# 2_power_a.net
KiCad netlist of a schematic drawn in EAGLE
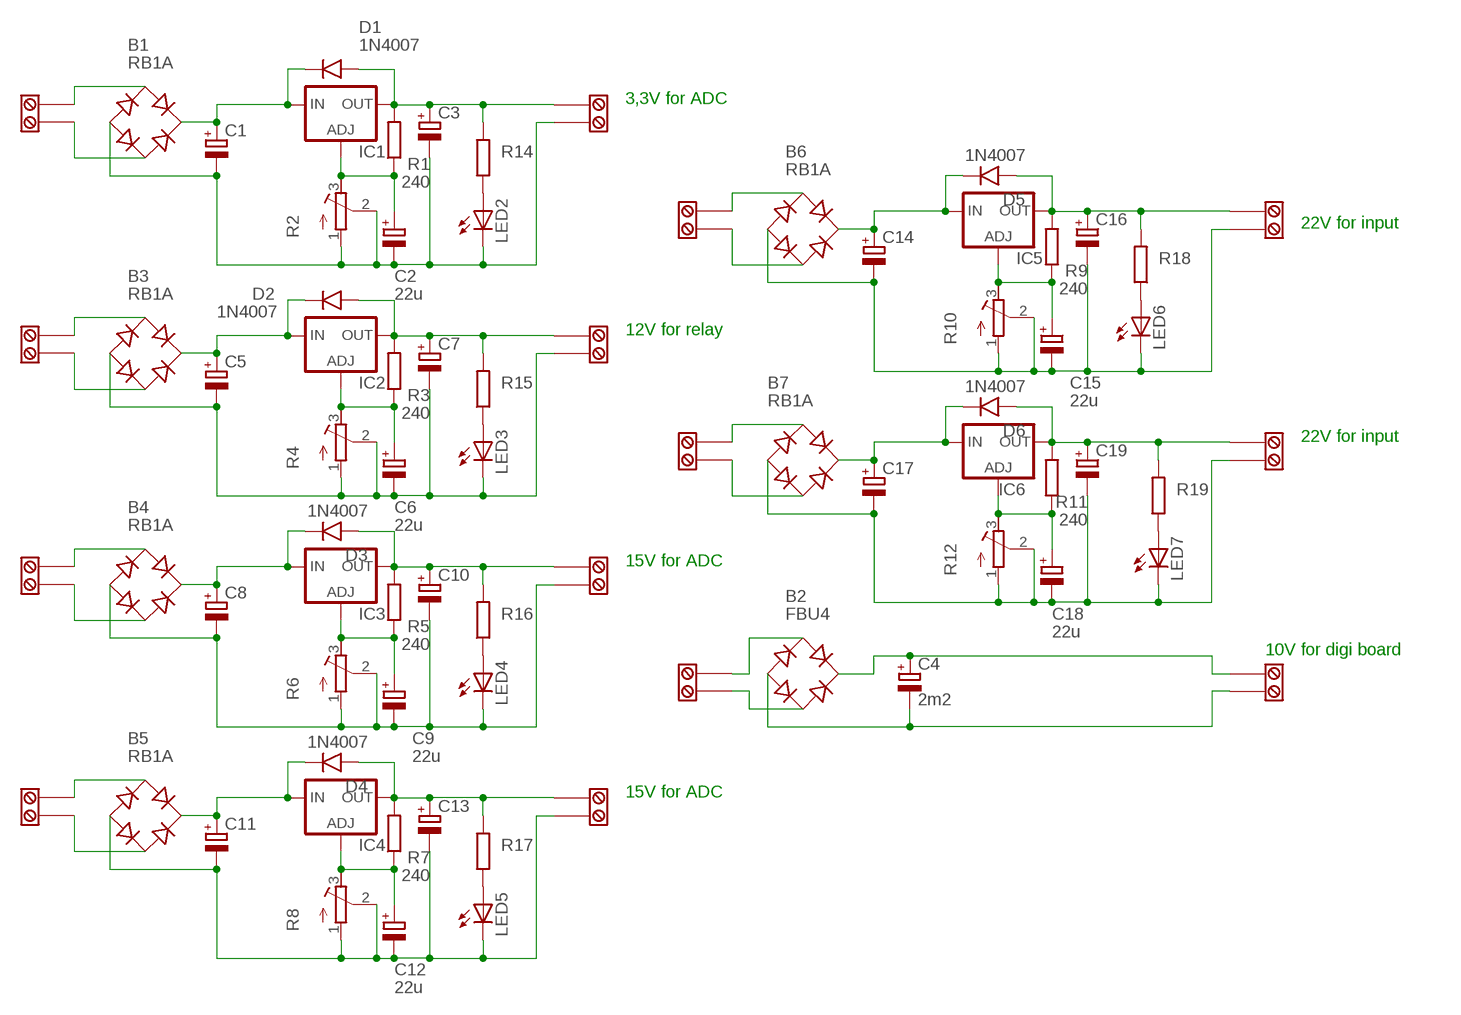
[diagram p0: schematic, sheet 1]

(export (version "E")
  (design (tool "Eeschema 10.0.6"))
  (components
    (comp (ref "B1")
      (value "RB1A")
      (footprint "eagle-import:RB1A")
      (libsource (lib "eagle-import") (part "RECTIFIER-RB1A"))
    )
    (comp (ref "B2")
      (value "FBU4")
      (footprint "eagle-import:FBU4")
      (libsource (lib "eagle-import") (part "RECTIFIER-FBU4"))
    )
    (comp (ref "B3")
      (value "RB1A")
      (footprint "eagle-import:RB1A")
      (libsource (lib "eagle-import") (part "RECTIFIER-RB1A"))
    )
    (comp (ref "B4")
      (value "RB1A")
      (footprint "eagle-import:RB1A")
      (libsource (lib "eagle-import") (part "RECTIFIER-RB1A"))
    )
    (comp (ref "B5")
      (value "RB1A")
      (footprint "eagle-import:RB1A")
      (libsource (lib "eagle-import") (part "RECTIFIER-RB1A"))
    )
    (comp (ref "B6")
      (value "RB1A")
      (footprint "eagle-import:RB1A")
      (libsource (lib "eagle-import") (part "RECTIFIER-RB1A"))
    )
    (comp (ref "B7")
      (value "RB1A")
      (footprint "eagle-import:RB1A")
      (libsource (lib "eagle-import") (part "RECTIFIER-RB1A"))
    )
    (comp (ref "C1")
      (value "CPOL-EUE5-10.5")
      (footprint "eagle-import:E5-10,5")
      (libsource (lib "eagle-import") (part "CPOL-EUE5-10.5"))
    )
    (comp (ref "C2")
      (value "22u")
      (footprint "eagle-import:E2,5-6")
      (libsource (lib "eagle-import") (part "CPOL-EUE2.5-6"))
    )
    (comp (ref "C3")
      (value "CPOL-EUE3.5-8")
      (footprint "eagle-import:E3,5-8")
      (libsource (lib "eagle-import") (part "CPOL-EUE3.5-8"))
    )
    (comp (ref "C4")
      (value "2m2")
      (footprint "eagle-import:E5-13")
      (libsource (lib "eagle-import") (part "CPOL-EUE5-13"))
    )
    (comp (ref "C5")
      (value "CPOL-EUE5-10.5")
      (footprint "eagle-import:E5-10,5")
      (libsource (lib "eagle-import") (part "CPOL-EUE5-10.5"))
    )
    (comp (ref "C6")
      (value "22u")
      (footprint "eagle-import:E2,5-6")
      (libsource (lib "eagle-import") (part "CPOL-EUE2.5-6"))
    )
    (comp (ref "C7")
      (value "CPOL-EUE3.5-8")
      (footprint "eagle-import:E3,5-8")
      (libsource (lib "eagle-import") (part "CPOL-EUE3.5-8"))
    )
    (comp (ref "C8")
      (value "CPOL-EUE5-10.5")
      (footprint "eagle-import:E5-10,5")
      (libsource (lib "eagle-import") (part "CPOL-EUE5-10.5"))
    )
    (comp (ref "C9")
      (value "22u")
      (footprint "eagle-import:E2,5-6")
      (libsource (lib "eagle-import") (part "CPOL-EUE2.5-6"))
    )
    (comp (ref "C10")
      (value "CPOL-EUE3.5-8")
      (footprint "eagle-import:E3,5-8")
      (libsource (lib "eagle-import") (part "CPOL-EUE3.5-8"))
    )
    (comp (ref "C11")
      (value "CPOL-EUE5-10.5")
      (footprint "eagle-import:E5-10,5")
      (libsource (lib "eagle-import") (part "CPOL-EUE5-10.5"))
    )
    (comp (ref "C12")
      (value "22u")
      (footprint "eagle-import:E2,5-6")
      (libsource (lib "eagle-import") (part "CPOL-EUE2.5-6"))
    )
    (comp (ref "C13")
      (value "CPOL-EUE3.5-8")
      (footprint "eagle-import:E3,5-8")
      (libsource (lib "eagle-import") (part "CPOL-EUE3.5-8"))
    )
    (comp (ref "C14")
      (value "CPOL-EUE5-10.5")
      (footprint "eagle-import:E5-10,5")
      (libsource (lib "eagle-import") (part "CPOL-EUE5-10.5"))
    )
    (comp (ref "C15")
      (value "22u")
      (footprint "eagle-import:E2,5-6")
      (libsource (lib "eagle-import") (part "CPOL-EUE2.5-6"))
    )
    (comp (ref "C16")
      (value "CPOL-EUE3.5-8")
      (footprint "eagle-import:E3,5-8")
      (libsource (lib "eagle-import") (part "CPOL-EUE3.5-8"))
    )
    (comp (ref "C17")
      (value "CPOL-EUE5-10.5")
      (footprint "eagle-import:E5-10,5")
      (libsource (lib "eagle-import") (part "CPOL-EUE5-10.5"))
    )
    (comp (ref "C18")
      (value "22u")
      (footprint "eagle-import:E2,5-6")
      (libsource (lib "eagle-import") (part "CPOL-EUE2.5-6"))
    )
    (comp (ref "C19")
      (value "CPOL-EUE3.5-8")
      (footprint "eagle-import:E3,5-8")
      (libsource (lib "eagle-import") (part "CPOL-EUE3.5-8"))
    )
    (comp (ref "D1")
      (value "1N4007")
      (footprint "eagle-import:DO41")
      (libsource (lib "eagle-import") (part "1N4007"))
    )
    (comp (ref "D2")
      (value "1N4007")
      (footprint "eagle-import:DO41")
      (libsource (lib "eagle-import") (part "1N4007"))
    )
    (comp (ref "D3")
      (value "1N4007")
      (footprint "eagle-import:DO41")
      (libsource (lib "eagle-import") (part "1N4007"))
    )
    (comp (ref "D4")
      (value "1N4007")
      (footprint "eagle-import:DO41")
      (libsource (lib "eagle-import") (part "1N4007"))
    )
    (comp (ref "D5")
      (value "1N4007")
      (footprint "eagle-import:DO41")
      (libsource (lib "eagle-import") (part "1N4007"))
    )
    (comp (ref "D6")
      (value "1N4007")
      (footprint "eagle-import:DO41")
      (libsource (lib "eagle-import") (part "1N4007"))
    )
    (comp (ref "IC1")
      (value "LM317TS")
      (footprint "eagle-import:317TS")
      (libsource (lib "eagle-import") (part "LM317TS"))
    )
    (comp (ref "IC2")
      (value "LM317TS")
      (footprint "eagle-import:317TS")
      (libsource (lib "eagle-import") (part "LM317TS"))
    )
    (comp (ref "IC3")
      (value "LM317TS")
      (footprint "eagle-import:317TS")
      (libsource (lib "eagle-import") (part "LM317TS"))
    )
    (comp (ref "IC4")
      (value "LM317TS")
      (footprint "eagle-import:317TS")
      (libsource (lib "eagle-import") (part "LM317TS"))
    )
    (comp (ref "IC5")
      (value "LM317TS")
      (footprint "eagle-import:317TS")
      (libsource (lib "eagle-import") (part "LM317TS"))
    )
    (comp (ref "IC6")
      (value "LM317TS")
      (footprint "eagle-import:317TS")
      (libsource (lib "eagle-import") (part "LM317TS"))
    )
    (comp (ref "LED2")
      (value "LED3MM")
      (footprint "eagle-import:LED3MM")
      (libsource (lib "eagle-import") (part "LED3MM"))
    )
    (comp (ref "LED3")
      (value "LED3MM")
      (footprint "eagle-import:LED3MM")
      (libsource (lib "eagle-import") (part "LED3MM"))
    )
    (comp (ref "LED4")
      (value "LED3MM")
      (footprint "eagle-import:LED3MM")
      (libsource (lib "eagle-import") (part "LED3MM"))
    )
    (comp (ref "LED5")
      (value "LED3MM")
      (footprint "eagle-import:LED3MM")
      (libsource (lib "eagle-import") (part "LED3MM"))
    )
    (comp (ref "LED6")
      (value "LED3MM")
      (footprint "eagle-import:LED3MM")
      (libsource (lib "eagle-import") (part "LED3MM"))
    )
    (comp (ref "LED7")
      (value "LED3MM")
      (footprint "eagle-import:LED3MM")
      (libsource (lib "eagle-import") (part "LED3MM"))
    )
    (comp (ref "R1")
      (value "240")
      (footprint "eagle-import:R_TR191")
      (libsource (lib "eagle-import") (part "R191"))
    )
    (comp (ref "R2")
      (value "R-TRIMM64Y")
      (footprint "eagle-import:RTRIM64Y")
      (libsource (lib "eagle-import") (part "R-TRIMM64Y"))
    )
    (comp (ref "R3")
      (value "240")
      (footprint "eagle-import:R_TR191")
      (libsource (lib "eagle-import") (part "R191"))
    )
    (comp (ref "R4")
      (value "R-TRIMM64Y")
      (footprint "eagle-import:RTRIM64Y")
      (libsource (lib "eagle-import") (part "R-TRIMM64Y"))
    )
    (comp (ref "R5")
      (value "240")
      (footprint "eagle-import:R_TR191")
      (libsource (lib "eagle-import") (part "R191"))
    )
    (comp (ref "R6")
      (value "R-TRIMM64Y")
      (footprint "eagle-import:RTRIM64Y")
      (libsource (lib "eagle-import") (part "R-TRIMM64Y"))
    )
    (comp (ref "R7")
      (value "240")
      (footprint "eagle-import:R_TR191")
      (libsource (lib "eagle-import") (part "R191"))
    )
    (comp (ref "R8")
      (value "R-TRIMM64Y")
      (footprint "eagle-import:RTRIM64Y")
      (libsource (lib "eagle-import") (part "R-TRIMM64Y"))
    )
    (comp (ref "R9")
      (value "240")
      (footprint "eagle-import:R_TR191")
      (libsource (lib "eagle-import") (part "R191"))
    )
    (comp (ref "R10")
      (value "R-TRIMM64Y")
      (footprint "eagle-import:RTRIM64Y")
      (libsource (lib "eagle-import") (part "R-TRIMM64Y"))
    )
    (comp (ref "R11")
      (value "240")
      (footprint "eagle-import:R_TR191")
      (libsource (lib "eagle-import") (part "R191"))
    )
    (comp (ref "R12")
      (value "R-TRIMM64Y")
      (footprint "eagle-import:RTRIM64Y")
      (libsource (lib "eagle-import") (part "R-TRIMM64Y"))
    )
    (comp (ref "R14")
      (value "R191S")
      (footprint "eagle-import:R_R191S")
      (libsource (lib "eagle-import") (part "R191S"))
    )
    (comp (ref "R15")
      (value "R191S")
      (footprint "eagle-import:R_R191S")
      (libsource (lib "eagle-import") (part "R191S"))
    )
    (comp (ref "R16")
      (value "R191S")
      (footprint "eagle-import:R_R191S")
      (libsource (lib "eagle-import") (part "R191S"))
    )
    (comp (ref "R17")
      (value "R191S")
      (footprint "eagle-import:R_R191S")
      (libsource (lib "eagle-import") (part "R191S"))
    )
    (comp (ref "R18")
      (value "R191S")
      (footprint "eagle-import:R_R191S")
      (libsource (lib "eagle-import") (part "R191S"))
    )
    (comp (ref "R19")
      (value "R191S")
      (footprint "eagle-import:R_R191S")
      (libsource (lib "eagle-import") (part "R191S"))
    )
    (comp (ref "U$1")
      (value "TERM_2P_SBP")
      (footprint "eagle-import:TERM-2P_381_BP")
      (libsource (lib "eagle-import") (part "TERM_2P_SBP"))
    )
    (comp (ref "U$2")
      (value "TERM_2P_SBP")
      (footprint "eagle-import:TERM-2P_381_BP")
      (libsource (lib "eagle-import") (part "TERM_2P_SBP"))
    )
    (comp (ref "U$3")
      (value "TERM_2P_SBP")
      (footprint "eagle-import:TERM-2P_381_BP")
      (libsource (lib "eagle-import") (part "TERM_2P_SBP"))
    )
    (comp (ref "U$4")
      (value "TERM_2P_SBP")
      (footprint "eagle-import:TERM-2P_381_BP")
      (libsource (lib "eagle-import") (part "TERM_2P_SBP"))
    )
    (comp (ref "U$5")
      (value "TERM_2P_SBP")
      (footprint "eagle-import:TERM-2P_381_BP")
      (libsource (lib "eagle-import") (part "TERM_2P_SBP"))
    )
    (comp (ref "U$6")
      (value "TERM_2P_SBP")
      (footprint "eagle-import:TERM-2P_381_BP")
      (libsource (lib "eagle-import") (part "TERM_2P_SBP"))
    )
    (comp (ref "U$7")
      (value "TERM_2P_SBP")
      (footprint "eagle-import:TERM-2P_381_BP")
      (libsource (lib "eagle-import") (part "TERM_2P_SBP"))
    )
    (comp (ref "U$8")
      (value "TERM_2P_SBP")
      (footprint "eagle-import:TERM-2P_381_BP")
      (libsource (lib "eagle-import") (part "TERM_2P_SBP"))
    )
    (comp (ref "U$9")
      (value "TERM_2P_SBP")
      (footprint "eagle-import:TERM-2P_381_BP")
      (libsource (lib "eagle-import") (part "TERM_2P_SBP"))
    )
    (comp (ref "U$10")
      (value "TERM_2P_SBP")
      (footprint "eagle-import:TERM-2P_381_BP")
      (libsource (lib "eagle-import") (part "TERM_2P_SBP"))
    )
    (comp (ref "U$11")
      (value "TERM_2P_SBP")
      (footprint "eagle-import:TERM-2P_381_BP")
      (libsource (lib "eagle-import") (part "TERM_2P_SBP"))
    )
    (comp (ref "U$12")
      (value "TERM_2P_SBP")
      (footprint "eagle-import:TERM-2P_381_BP")
      (libsource (lib "eagle-import") (part "TERM_2P_SBP"))
    )
    (comp (ref "U$13")
      (value "TERM_2P_SBP")
      (footprint "eagle-import:TERM-2P_381_BP")
      (libsource (lib "eagle-import") (part "TERM_2P_SBP"))
    )
    (comp (ref "U$14")
      (value "TERM_2P_SBP")
      (footprint "eagle-import:TERM-2P_381_BP")
      (libsource (lib "eagle-import") (part "TERM_2P_SBP"))
    )
  )
  (nets
    (net (code "1") (name "Net-(B1-PadAC1)") (class "Default")
      (node (ref "B1") (pin "AC1") (pinfunction "AC1_AC1") (pintype "passive"))
      (node (ref "U$2") (pin "P$1") (pinfunction "P$1_P$1") (pintype "bidirectional"))
    )
    (net (code "2") (name "Net-(B1-PadAC2)") (class "Default")
      (node (ref "B1") (pin "AC2") (pinfunction "AC2_AC2") (pintype "passive"))
      (node (ref "U$2") (pin "P$2") (pinfunction "P$2_P$2") (pintype "bidirectional"))
    )
    (net (code "3") (name "Net-(B2-Pad+)") (class "Default")
      (node (ref "B2") (pin "+") (pinfunction "+_+") (pintype "passive"))
      (node (ref "C4") (pin "+") (pinfunction "+_+") (pintype "passive"))
      (node (ref "U$3") (pin "P$2") (pinfunction "P$2_P$2") (pintype "bidirectional"))
    )
    (net (code "4") (name "Net-(B2-Pad-)") (class "Default")
      (node (ref "B2") (pin "-") (pinfunction "-_-") (pintype "passive"))
      (node (ref "C4") (pin "-") (pinfunction "-_-") (pintype "passive"))
      (node (ref "U$3") (pin "P$1") (pinfunction "P$1_P$1") (pintype "bidirectional"))
    )
    (net (code "5") (name "Net-(B2-PadAC1)") (class "Default")
      (node (ref "B2") (pin "AC1") (pinfunction "AC1_AC1") (pintype "passive"))
      (node (ref "U$1") (pin "P$1") (pinfunction "P$1_P$1") (pintype "bidirectional"))
    )
    (net (code "6") (name "Net-(B2-PadAC2)") (class "Default")
      (node (ref "B2") (pin "AC2") (pinfunction "AC2_AC2") (pintype "passive"))
      (node (ref "U$1") (pin "P$2") (pinfunction "P$2_P$2") (pintype "bidirectional"))
    )
    (net (code "7") (name "Net-(B3-PadAC1)") (class "Default")
      (node (ref "B3") (pin "AC1") (pinfunction "AC1_AC1") (pintype "passive"))
      (node (ref "U$5") (pin "P$1") (pinfunction "P$1_P$1") (pintype "bidirectional"))
    )
    (net (code "8") (name "Net-(B3-PadAC2)") (class "Default")
      (node (ref "B3") (pin "AC2") (pinfunction "AC2_AC2") (pintype "passive"))
      (node (ref "U$5") (pin "P$2") (pinfunction "P$2_P$2") (pintype "bidirectional"))
    )
    (net (code "9") (name "Net-(B4-PadAC1)") (class "Default")
      (node (ref "B4") (pin "AC1") (pinfunction "AC1_AC1") (pintype "passive"))
      (node (ref "U$7") (pin "P$1") (pinfunction "P$1_P$1") (pintype "bidirectional"))
    )
    (net (code "10") (name "Net-(B4-PadAC2)") (class "Default")
      (node (ref "B4") (pin "AC2") (pinfunction "AC2_AC2") (pintype "passive"))
      (node (ref "U$7") (pin "P$2") (pinfunction "P$2_P$2") (pintype "bidirectional"))
    )
    (net (code "11") (name "Net-(B5-PadAC1)") (class "Default")
      (node (ref "B5") (pin "AC1") (pinfunction "AC1_AC1") (pintype "passive"))
      (node (ref "U$9") (pin "P$1") (pinfunction "P$1_P$1") (pintype "bidirectional"))
    )
    (net (code "12") (name "Net-(B5-PadAC2)") (class "Default")
      (node (ref "B5") (pin "AC2") (pinfunction "AC2_AC2") (pintype "passive"))
      (node (ref "U$9") (pin "P$2") (pinfunction "P$2_P$2") (pintype "bidirectional"))
    )
    (net (code "13") (name "Net-(B6-PadAC1)") (class "Default")
      (node (ref "B6") (pin "AC1") (pinfunction "AC1_AC1") (pintype "passive"))
      (node (ref "U$11") (pin "P$1") (pinfunction "P$1_P$1") (pintype "bidirectional"))
    )
    (net (code "14") (name "Net-(B6-PadAC2)") (class "Default")
      (node (ref "B6") (pin "AC2") (pinfunction "AC2_AC2") (pintype "passive"))
      (node (ref "U$11") (pin "P$2") (pinfunction "P$2_P$2") (pintype "bidirectional"))
    )
    (net (code "15") (name "Net-(B7-PadAC1)") (class "Default")
      (node (ref "B7") (pin "AC1") (pinfunction "AC1_AC1") (pintype "passive"))
      (node (ref "U$13") (pin "P$1") (pinfunction "P$1_P$1") (pintype "bidirectional"))
    )
    (net (code "16") (name "Net-(B7-PadAC2)") (class "Default")
      (node (ref "B7") (pin "AC2") (pinfunction "AC2_AC2") (pintype "passive"))
      (node (ref "U$13") (pin "P$2") (pinfunction "P$2_P$2") (pintype "bidirectional"))
    )
    (net (code "17") (name "Net-(IC1-ADJ)") (class "Default")
      (node (ref "C2") (pin "+") (pinfunction "+_+") (pintype "passive"))
      (node (ref "IC1") (pin "1") (pinfunction "ADJ_1") (pintype "input"))
      (node (ref "R1") (pin "P$1") (pinfunction "1_P$1") (pintype "passive"))
      (node (ref "R2") (pin "3") (pinfunction "A_3") (pintype "passive"))
    )
    (net (code "18") (name "Net-(IC1-IN)") (class "Default")
      (node (ref "B1") (pin "+") (pinfunction "+_+") (pintype "passive"))
      (node (ref "C1") (pin "+") (pinfunction "+_+") (pintype "passive"))
      (node (ref "D1") (pin "K") (pinfunction "K_K") (pintype "output"))
      (node (ref "IC1") (pin "3") (pinfunction "IN_3") (pintype "input"))
    )
    (net (code "19") (name "Net-(IC1-OUT)") (class "Default")
      (node (ref "C3") (pin "+") (pinfunction "+_+") (pintype "passive"))
      (node (ref "D1") (pin "A") (pinfunction "A_A") (pintype "input"))
      (node (ref "IC1") (pin "2") (pinfunction "OUT_2") (pintype "passive"))
      (node (ref "R1") (pin "P$2") (pinfunction "2_P$2") (pintype "passive"))
      (node (ref "R14") (pin "P$2") (pinfunction "2_P$2") (pintype "passive"))
      (node (ref "U$4") (pin "P$2") (pinfunction "P$2_P$2") (pintype "bidirectional"))
    )
    (net (code "20") (name "Net-(IC2-ADJ)") (class "Default")
      (node (ref "C6") (pin "+") (pinfunction "+_+") (pintype "passive"))
      (node (ref "IC2") (pin "1") (pinfunction "ADJ_1") (pintype "input"))
      (node (ref "R3") (pin "P$1") (pinfunction "1_P$1") (pintype "passive"))
      (node (ref "R4") (pin "3") (pinfunction "A_3") (pintype "passive"))
    )
    (net (code "21") (name "Net-(IC2-IN)") (class "Default")
      (node (ref "B3") (pin "+") (pinfunction "+_+") (pintype "passive"))
      (node (ref "C5") (pin "+") (pinfunction "+_+") (pintype "passive"))
      (node (ref "D2") (pin "K") (pinfunction "K_K") (pintype "output"))
      (node (ref "IC2") (pin "3") (pinfunction "IN_3") (pintype "input"))
    )
    (net (code "22") (name "Net-(IC2-OUT)") (class "Default")
      (node (ref "C7") (pin "+") (pinfunction "+_+") (pintype "passive"))
      (node (ref "D2") (pin "A") (pinfunction "A_A") (pintype "input"))
      (node (ref "IC2") (pin "2") (pinfunction "OUT_2") (pintype "passive"))
      (node (ref "R15") (pin "P$2") (pinfunction "2_P$2") (pintype "passive"))
      (node (ref "R3") (pin "P$2") (pinfunction "2_P$2") (pintype "passive"))
      (node (ref "U$6") (pin "P$2") (pinfunction "P$2_P$2") (pintype "bidirectional"))
    )
    (net (code "23") (name "Net-(IC3-ADJ)") (class "Default")
      (node (ref "C9") (pin "+") (pinfunction "+_+") (pintype "passive"))
      (node (ref "IC3") (pin "1") (pinfunction "ADJ_1") (pintype "input"))
      (node (ref "R5") (pin "P$1") (pinfunction "1_P$1") (pintype "passive"))
      (node (ref "R6") (pin "3") (pinfunction "A_3") (pintype "passive"))
    )
    (net (code "24") (name "Net-(IC3-IN)") (class "Default")
      (node (ref "B4") (pin "+") (pinfunction "+_+") (pintype "passive"))
      (node (ref "C8") (pin "+") (pinfunction "+_+") (pintype "passive"))
      (node (ref "D3") (pin "K") (pinfunction "K_K") (pintype "output"))
      (node (ref "IC3") (pin "3") (pinfunction "IN_3") (pintype "input"))
    )
    (net (code "25") (name "Net-(IC3-OUT)") (class "Default")
      (node (ref "C10") (pin "+") (pinfunction "+_+") (pintype "passive"))
      (node (ref "D3") (pin "A") (pinfunction "A_A") (pintype "input"))
      (node (ref "IC3") (pin "2") (pinfunction "OUT_2") (pintype "passive"))
      (node (ref "R16") (pin "P$2") (pinfunction "2_P$2") (pintype "passive"))
      (node (ref "R5") (pin "P$2") (pinfunction "2_P$2") (pintype "passive"))
      (node (ref "U$8") (pin "P$2") (pinfunction "P$2_P$2") (pintype "bidirectional"))
    )
    (net (code "26") (name "Net-(IC4-ADJ)") (class "Default")
      (node (ref "C12") (pin "+") (pinfunction "+_+") (pintype "passive"))
      (node (ref "IC4") (pin "1") (pinfunction "ADJ_1") (pintype "input"))
      (node (ref "R7") (pin "P$1") (pinfunction "1_P$1") (pintype "passive"))
      (node (ref "R8") (pin "3") (pinfunction "A_3") (pintype "passive"))
    )
    (net (code "27") (name "Net-(IC4-IN)") (class "Default")
      (node (ref "B5") (pin "+") (pinfunction "+_+") (pintype "passive"))
      (node (ref "C11") (pin "+") (pinfunction "+_+") (pintype "passive"))
      (node (ref "D4") (pin "K") (pinfunction "K_K") (pintype "output"))
      (node (ref "IC4") (pin "3") (pinfunction "IN_3") (pintype "input"))
    )
    (net (code "28") (name "Net-(IC4-OUT)") (class "Default")
      (node (ref "C13") (pin "+") (pinfunction "+_+") (pintype "passive"))
      (node (ref "D4") (pin "A") (pinfunction "A_A") (pintype "input"))
      (node (ref "IC4") (pin "2") (pinfunction "OUT_2") (pintype "passive"))
      (node (ref "R17") (pin "P$2") (pinfunction "2_P$2") (pintype "passive"))
      (node (ref "R7") (pin "P$2") (pinfunction "2_P$2") (pintype "passive"))
      (node (ref "U$10") (pin "P$2") (pinfunction "P$2_P$2") (pintype "bidirectional"))
    )
    (net (code "29") (name "Net-(IC5-ADJ)") (class "Default")
      (node (ref "C15") (pin "+") (pinfunction "+_+") (pintype "passive"))
      (node (ref "IC5") (pin "1") (pinfunction "ADJ_1") (pintype "input"))
      (node (ref "R10") (pin "3") (pinfunction "A_3") (pintype "passive"))
      (node (ref "R9") (pin "P$1") (pinfunction "1_P$1") (pintype "passive"))
    )
    (net (code "30") (name "Net-(IC5-IN)") (class "Default")
      (node (ref "B6") (pin "+") (pinfunction "+_+") (pintype "passive"))
      (node (ref "C14") (pin "+") (pinfunction "+_+") (pintype "passive"))
      (node (ref "D5") (pin "K") (pinfunction "K_K") (pintype "output"))
      (node (ref "IC5") (pin "3") (pinfunction "IN_3") (pintype "input"))
    )
    (net (code "31") (name "Net-(IC5-OUT)") (class "Default")
      (node (ref "C16") (pin "+") (pinfunction "+_+") (pintype "passive"))
      (node (ref "D5") (pin "A") (pinfunction "A_A") (pintype "input"))
      (node (ref "IC5") (pin "2") (pinfunction "OUT_2") (pintype "passive"))
      (node (ref "R18") (pin "P$2") (pinfunction "2_P$2") (pintype "passive"))
      (node (ref "R9") (pin "P$2") (pinfunction "2_P$2") (pintype "passive"))
      (node (ref "U$12") (pin "P$2") (pinfunction "P$2_P$2") (pintype "bidirectional"))
    )
    (net (code "32") (name "Net-(IC6-ADJ)") (class "Default")
      (node (ref "C18") (pin "+") (pinfunction "+_+") (pintype "passive"))
      (node (ref "IC6") (pin "1") (pinfunction "ADJ_1") (pintype "input"))
      (node (ref "R11") (pin "P$1") (pinfunction "1_P$1") (pintype "passive"))
      (node (ref "R12") (pin "3") (pinfunction "A_3") (pintype "passive"))
    )
    (net (code "33") (name "Net-(IC6-IN)") (class "Default")
      (node (ref "B7") (pin "+") (pinfunction "+_+") (pintype "passive"))
      (node (ref "C17") (pin "+") (pinfunction "+_+") (pintype "passive"))
      (node (ref "D6") (pin "K") (pinfunction "K_K") (pintype "output"))
      (node (ref "IC6") (pin "3") (pinfunction "IN_3") (pintype "input"))
    )
    (net (code "34") (name "Net-(IC6-OUT)") (class "Default")
      (node (ref "C19") (pin "+") (pinfunction "+_+") (pintype "passive"))
      (node (ref "D6") (pin "A") (pinfunction "A_A") (pintype "input"))
      (node (ref "IC6") (pin "2") (pinfunction "OUT_2") (pintype "passive"))
      (node (ref "R11") (pin "P$2") (pinfunction "2_P$2") (pintype "passive"))
      (node (ref "R19") (pin "P$2") (pinfunction "2_P$2") (pintype "passive"))
      (node (ref "U$14") (pin "P$2") (pinfunction "P$2_P$2") (pintype "bidirectional"))
    )
    (net (code "35") (name "Net-(LED2-C)") (class "Default")
      (node (ref "B1") (pin "-") (pinfunction "-_-") (pintype "passive"))
      (node (ref "C1") (pin "-") (pinfunction "-_-") (pintype "passive"))
      (node (ref "C2") (pin "-") (pinfunction "-_-") (pintype "passive"))
      (node (ref "C3") (pin "-") (pinfunction "-_-") (pintype "passive"))
      (node (ref "LED2") (pin "K") (pinfunction "C_K") (pintype "passive"))
      (node (ref "R2") (pin "1") (pinfunction "E_1") (pintype "passive"))
      (node (ref "R2") (pin "2") (pinfunction "S_2") (pintype "passive"))
      (node (ref "U$4") (pin "P$1") (pinfunction "P$1_P$1") (pintype "bidirectional"))
    )
    (net (code "36") (name "Net-(LED3-C)") (class "Default")
      (node (ref "B3") (pin "-") (pinfunction "-_-") (pintype "passive"))
      (node (ref "C5") (pin "-") (pinfunction "-_-") (pintype "passive"))
      (node (ref "C6") (pin "-") (pinfunction "-_-") (pintype "passive"))
      (node (ref "C7") (pin "-") (pinfunction "-_-") (pintype "passive"))
      (node (ref "LED3") (pin "K") (pinfunction "C_K") (pintype "passive"))
      (node (ref "R4") (pin "1") (pinfunction "E_1") (pintype "passive"))
      (node (ref "R4") (pin "2") (pinfunction "S_2") (pintype "passive"))
      (node (ref "U$6") (pin "P$1") (pinfunction "P$1_P$1") (pintype "bidirectional"))
    )
    (net (code "37") (name "Net-(LED4-C)") (class "Default")
      (node (ref "B4") (pin "-") (pinfunction "-_-") (pintype "passive"))
      (node (ref "C10") (pin "-") (pinfunction "-_-") (pintype "passive"))
      (node (ref "C8") (pin "-") (pinfunction "-_-") (pintype "passive"))
      (node (ref "C9") (pin "-") (pinfunction "-_-") (pintype "passive"))
      (node (ref "LED4") (pin "K") (pinfunction "C_K") (pintype "passive"))
      (node (ref "R6") (pin "1") (pinfunction "E_1") (pintype "passive"))
      (node (ref "R6") (pin "2") (pinfunction "S_2") (pintype "passive"))
      (node (ref "U$8") (pin "P$1") (pinfunction "P$1_P$1") (pintype "bidirectional"))
    )
    (net (code "38") (name "Net-(LED5-C)") (class "Default")
      (node (ref "B5") (pin "-") (pinfunction "-_-") (pintype "passive"))
      (node (ref "C11") (pin "-") (pinfunction "-_-") (pintype "passive"))
      (node (ref "C12") (pin "-") (pinfunction "-_-") (pintype "passive"))
      (node (ref "C13") (pin "-") (pinfunction "-_-") (pintype "passive"))
      (node (ref "LED5") (pin "K") (pinfunction "C_K") (pintype "passive"))
      (node (ref "R8") (pin "1") (pinfunction "E_1") (pintype "passive"))
      (node (ref "R8") (pin "2") (pinfunction "S_2") (pintype "passive"))
      (node (ref "U$10") (pin "P$1") (pinfunction "P$1_P$1") (pintype "bidirectional"))
    )
    (net (code "39") (name "Net-(LED6-C)") (class "Default")
      (node (ref "B6") (pin "-") (pinfunction "-_-") (pintype "passive"))
      (node (ref "C14") (pin "-") (pinfunction "-_-") (pintype "passive"))
      (node (ref "C15") (pin "-") (pinfunction "-_-") (pintype "passive"))
      (node (ref "C16") (pin "-") (pinfunction "-_-") (pintype "passive"))
      (node (ref "LED6") (pin "K") (pinfunction "C_K") (pintype "passive"))
      (node (ref "R10") (pin "1") (pinfunction "E_1") (pintype "passive"))
      (node (ref "R10") (pin "2") (pinfunction "S_2") (pintype "passive"))
      (node (ref "U$12") (pin "P$1") (pinfunction "P$1_P$1") (pintype "bidirectional"))
    )
    (net (code "40") (name "Net-(LED7-C)") (class "Default")
      (node (ref "B7") (pin "-") (pinfunction "-_-") (pintype "passive"))
      (node (ref "C17") (pin "-") (pinfunction "-_-") (pintype "passive"))
      (node (ref "C18") (pin "-") (pinfunction "-_-") (pintype "passive"))
      (node (ref "C19") (pin "-") (pinfunction "-_-") (pintype "passive"))
      (node (ref "LED7") (pin "K") (pinfunction "C_K") (pintype "passive"))
      (node (ref "R12") (pin "1") (pinfunction "E_1") (pintype "passive"))
      (node (ref "R12") (pin "2") (pinfunction "S_2") (pintype "passive"))
      (node (ref "U$14") (pin "P$1") (pinfunction "P$1_P$1") (pintype "bidirectional"))
    )
    (net (code "41") (name "Net-(R14-1)") (class "Default")
      (node (ref "LED2") (pin "A") (pinfunction "A_A") (pintype "passive"))
      (node (ref "R14") (pin "P$1") (pinfunction "1_P$1") (pintype "passive"))
    )
    (net (code "42") (name "Net-(R15-1)") (class "Default")
      (node (ref "LED3") (pin "A") (pinfunction "A_A") (pintype "passive"))
      (node (ref "R15") (pin "P$1") (pinfunction "1_P$1") (pintype "passive"))
    )
    (net (code "43") (name "Net-(R16-1)") (class "Default")
      (node (ref "LED4") (pin "A") (pinfunction "A_A") (pintype "passive"))
      (node (ref "R16") (pin "P$1") (pinfunction "1_P$1") (pintype "passive"))
    )
    (net (code "44") (name "Net-(R17-1)") (class "Default")
      (node (ref "LED5") (pin "A") (pinfunction "A_A") (pintype "passive"))
      (node (ref "R17") (pin "P$1") (pinfunction "1_P$1") (pintype "passive"))
    )
    (net (code "45") (name "Net-(R18-1)") (class "Default")
      (node (ref "LED6") (pin "A") (pinfunction "A_A") (pintype "passive"))
      (node (ref "R18") (pin "P$1") (pinfunction "1_P$1") (pintype "passive"))
    )
    (net (code "46") (name "Net-(R19-1)") (class "Default")
      (node (ref "LED7") (pin "A") (pinfunction "A_A") (pintype "passive"))
      (node (ref "R19") (pin "P$1") (pinfunction "1_P$1") (pintype "passive"))
    )
  )
)
